# Cisco-Console-CP2102-Piggyback.net
KiCad netlist of a schematic drawn in EAGLE
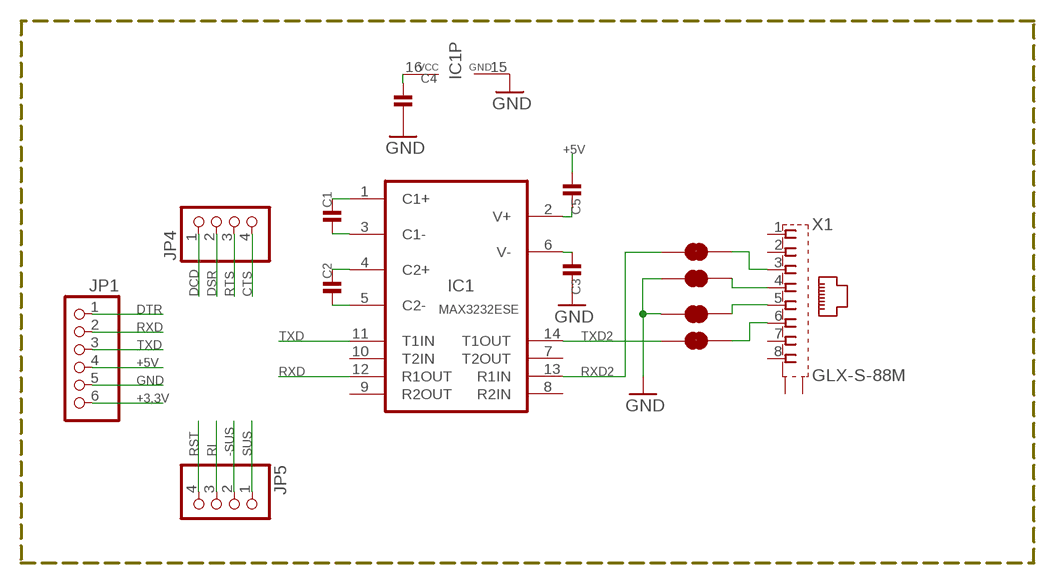
[diagram p0: schematic, sheet 1]

(export (version "E")
  (design (tool "Eeschema 10.0.6"))
  (components
    (comp (ref "C1")
      (value "MICROBUILDER_CAP_CERAMIC0402")
      (footprint "eagle-import:MICROBUILDER_0402")
      (libsource (lib "eagle-import") (part "MICROBUILDER_CAP_CERAMIC0402"))
    )
    (comp (ref "C2")
      (value "MICROBUILDER_CAP_CERAMIC0402")
      (footprint "eagle-import:MICROBUILDER_0402")
      (libsource (lib "eagle-import") (part "MICROBUILDER_CAP_CERAMIC0402"))
    )
    (comp (ref "C3")
      (value "MICROBUILDER_CAP_CERAMIC0402")
      (footprint "eagle-import:MICROBUILDER_0402")
      (libsource (lib "eagle-import") (part "MICROBUILDER_CAP_CERAMIC0402"))
    )
    (comp (ref "C4")
      (value "MICROBUILDER_CAP_CERAMIC0402")
      (footprint "eagle-import:MICROBUILDER_0402")
      (libsource (lib "eagle-import") (part "MICROBUILDER_CAP_CERAMIC0402"))
    )
    (comp (ref "C5")
      (value "MICROBUILDER_CAP_CERAMIC0402")
      (footprint "eagle-import:MICROBUILDER_0402")
      (libsource (lib "eagle-import") (part "MICROBUILDER_CAP_CERAMIC0402"))
    )
    (comp (ref "IC1")
      (value "MAX3232ESE")
      (footprint "eagle-import:SO16")
      (fields (field (name "MF") "MAXIM"))
      (libsource (lib "eagle-import") (part "MAX3232SEE"))
    )
    (comp (ref "JP1")
      (value "PINHD-1X6")
      (footprint "eagle-import:1X06")
      (libsource (lib "eagle-import") (part "PINHD-1X6"))
    )
    (comp (ref "JP4")
      (value "PINHD-1X4")
      (footprint "eagle-import:1X04")
      (libsource (lib "eagle-import") (part "PINHD-1X4"))
    )
    (comp (ref "JP5")
      (value "PINHD-1X4")
      (footprint "eagle-import:1X04")
      (libsource (lib "eagle-import") (part "PINHD-1X4"))
    )
    (comp (ref "JP6")
      (value "JUMPER-SMT_2_NC_TRACE_NO-SILK")
      (footprint "eagle-import:SMT-JUMPER_2_NC_TRACE_NO-SILK")
      (libsource (lib "eagle-import") (part "JUMPER-SMT_2_NC_TRACE_NO-SILK"))
    )
    (comp (ref "JP7")
      (value "JUMPER-SMT_2_NC_TRACE_NO-SILK")
      (footprint "eagle-import:SMT-JUMPER_2_NC_TRACE_NO-SILK")
      (libsource (lib "eagle-import") (part "JUMPER-SMT_2_NC_TRACE_NO-SILK"))
    )
    (comp (ref "JP8")
      (value "JUMPER-SMT_2_NC_TRACE_NO-SILK")
      (footprint "eagle-import:SMT-JUMPER_2_NC_TRACE_NO-SILK")
      (libsource (lib "eagle-import") (part "JUMPER-SMT_2_NC_TRACE_NO-SILK"))
    )
    (comp (ref "JP9")
      (value "JUMPER-SMT_2_NC_TRACE_NO-SILK")
      (footprint "eagle-import:SMT-JUMPER_2_NC_TRACE_NO-SILK")
      (libsource (lib "eagle-import") (part "JUMPER-SMT_2_NC_TRACE_NO-SILK"))
    )
    (comp (ref "X1")
      (value "GLX-S-88M")
      (footprint "eagle-import:GLX-S-88M")
      (libsource (lib "eagle-import") (part "GLX-S-88M"))
    )
  )
  (nets
    (net (code "1") (name "/+3,3V") (class "Default")
      (node (ref "JP1") (pin "6") (pinfunction "6_6") (pintype "passive"))
    )
    (net (code "2") (name "/+5V") (class "Default")
      (node (ref "C5") (pin "1") (pinfunction "P$1_1") (pintype "passive"))
      (node (ref "JP1") (pin "4") (pinfunction "4_4") (pintype "passive"))
    )
    (net (code "3") (name "/-SUS") (class "Default")
      (node (ref "JP5") (pin "2") (pinfunction "2_2") (pintype "passive"))
    )
    (net (code "4") (name "/CTS") (class "Default")
      (node (ref "JP4") (pin "4") (pinfunction "4_4") (pintype "passive"))
    )
    (net (code "5") (name "/DCD") (class "Default")
      (node (ref "JP4") (pin "1") (pinfunction "1_1") (pintype "passive"))
    )
    (net (code "6") (name "/DSR") (class "Default")
      (node (ref "JP4") (pin "2") (pinfunction "2_2") (pintype "passive"))
    )
    (net (code "7") (name "/DTR") (class "Default")
      (node (ref "JP1") (pin "1") (pinfunction "1_1") (pintype "passive"))
    )
    (net (code "8") (name "/RI") (class "Default")
      (node (ref "JP5") (pin "3") (pinfunction "3_3") (pintype "passive"))
    )
    (net (code "9") (name "/RST") (class "Default")
      (node (ref "JP5") (pin "4") (pinfunction "4_4") (pintype "passive"))
    )
    (net (code "10") (name "/RTS") (class "Default")
      (node (ref "JP4") (pin "3") (pinfunction "3_3") (pintype "passive"))
    )
    (net (code "11") (name "/RXD") (class "Default")
      (node (ref "IC1") (pin "12") (pinfunction "R1OUT_12") (pintype "output"))
      (node (ref "JP1") (pin "2") (pinfunction "2_2") (pintype "passive"))
    )
    (net (code "12") (name "/RXD2") (class "Default")
      (node (ref "IC1") (pin "13") (pinfunction "R1IN_13") (pintype "input"))
      (node (ref "JP6") (pin "1") (pinfunction "1_1") (pintype "passive"))
    )
    (net (code "13") (name "/SUS") (class "Default")
      (node (ref "JP5") (pin "1") (pinfunction "1_1") (pintype "passive"))
    )
    (net (code "14") (name "/TXD") (class "Default")
      (node (ref "IC1") (pin "11") (pinfunction "T1IN_11") (pintype "input"))
      (node (ref "JP1") (pin "3") (pinfunction "3_3") (pintype "passive"))
    )
    (net (code "15") (name "/TXD2") (class "Default")
      (node (ref "IC1") (pin "14") (pinfunction "T1OUT_14") (pintype "output"))
      (node (ref "JP9") (pin "1") (pinfunction "1_1") (pintype "passive"))
    )
    (net (code "16") (name "GND") (class "Default")
      (node (ref "C3") (pin "2") (pinfunction "P$2_2") (pintype "passive"))
      (node (ref "C4") (pin "2") (pinfunction "P$2_2") (pintype "passive"))
      (node (ref "IC1") (pin "15") (pinfunction "GND_15") (pintype "power_in"))
      (node (ref "JP1") (pin "5") (pinfunction "5_5") (pintype "passive"))
      (node (ref "JP7") (pin "1") (pinfunction "1_1") (pintype "passive"))
      (node (ref "JP8") (pin "1") (pinfunction "1_1") (pintype "passive"))
    )
    (net (code "17") (name "Net-(C1-P$1)") (class "Default")
      (node (ref "C1") (pin "1") (pinfunction "P$1_1") (pintype "passive"))
      (node (ref "IC1") (pin "1") (pinfunction "C1+_1") (pintype "bidirectional"))
    )
    (net (code "18") (name "Net-(C1-P$2)") (class "Default")
      (node (ref "C1") (pin "2") (pinfunction "P$2_2") (pintype "passive"))
      (node (ref "IC1") (pin "3") (pinfunction "C1-_3") (pintype "bidirectional"))
    )
    (net (code "19") (name "Net-(C2-P$1)") (class "Default")
      (node (ref "C2") (pin "1") (pinfunction "P$1_1") (pintype "passive"))
      (node (ref "IC1") (pin "4") (pinfunction "C2+_4") (pintype "bidirectional"))
    )
    (net (code "20") (name "Net-(C2-P$2)") (class "Default")
      (node (ref "C2") (pin "2") (pinfunction "P$2_2") (pintype "passive"))
      (node (ref "IC1") (pin "5") (pinfunction "C2-_5") (pintype "bidirectional"))
    )
    (net (code "21") (name "Net-(C3-P$1)") (class "Default")
      (node (ref "C3") (pin "1") (pinfunction "P$1_1") (pintype "passive"))
      (node (ref "IC1") (pin "6") (pinfunction "V-_6") (pintype "bidirectional"))
    )
    (net (code "22") (name "Net-(C4-P$1)") (class "Default")
      (node (ref "C4") (pin "1") (pinfunction "P$1_1") (pintype "passive"))
      (node (ref "IC1") (pin "16") (pinfunction "VCC_16") (pintype "power_in"))
    )
    (net (code "23") (name "Net-(C5-P$2)") (class "Default")
      (node (ref "C5") (pin "2") (pinfunction "P$2_2") (pintype "passive"))
      (node (ref "IC1") (pin "2") (pinfunction "V+_2") (pintype "bidirectional"))
    )
    (net (code "24") (name "Net-(JP6-Pad2)") (class "Default")
      (node (ref "JP6") (pin "2") (pinfunction "2_2") (pintype "passive"))
      (node (ref "X1") (pin "3") (pinfunction "3_3") (pintype "passive"))
    )
    (net (code "25") (name "Net-(JP7-Pad2)") (class "Default")
      (node (ref "JP7") (pin "2") (pinfunction "2_2") (pintype "passive"))
      (node (ref "X1") (pin "4") (pinfunction "4_4") (pintype "passive"))
    )
    (net (code "26") (name "Net-(JP8-Pad2)") (class "Default")
      (node (ref "JP8") (pin "2") (pinfunction "2_2") (pintype "passive"))
      (node (ref "X1") (pin "5") (pinfunction "5_5") (pintype "passive"))
    )
    (net (code "27") (name "Net-(JP9-Pad2)") (class "Default")
      (node (ref "JP9") (pin "2") (pinfunction "2_2") (pintype "passive"))
      (node (ref "X1") (pin "6") (pinfunction "6_6") (pintype "passive"))
    )
    (net (code "28") (name "unconnected-(IC1A-R2IN-Pad8)") (class "Default")
      (node (ref "IC1") (pin "8") (pinfunction "R2IN_8") (pintype "input"))
    )
    (net (code "29") (name "unconnected-(IC1A-R2OUT-Pad9)") (class "Default")
      (node (ref "IC1") (pin "9") (pinfunction "R2OUT_9") (pintype "output"))
    )
    (net (code "30") (name "unconnected-(IC1A-T2IN-Pad10)") (class "Default")
      (node (ref "IC1") (pin "10") (pinfunction "T2IN_10") (pintype "input"))
    )
    (net (code "31") (name "unconnected-(IC1A-T2OUT-Pad7)") (class "Default")
      (node (ref "IC1") (pin "7") (pinfunction "T2OUT_7") (pintype "output"))
    )
    (net (code "32") (name "unconnected-(X1-Pad1)") (class "Default")
      (node (ref "X1") (pin "1") (pinfunction "1_1") (pintype "passive"))
    )
    (net (code "33") (name "unconnected-(X1-Pad2)") (class "Default")
      (node (ref "X1") (pin "2") (pinfunction "2_2") (pintype "passive"))
    )
    (net (code "34") (name "unconnected-(X1-Pad7)") (class "Default")
      (node (ref "X1") (pin "7") (pinfunction "7_7") (pintype "passive"))
    )
    (net (code "35") (name "unconnected-(X1-Pad8)") (class "Default")
      (node (ref "X1") (pin "8") (pinfunction "8_8") (pintype "passive"))
    )
    (net (code "36") (name "unconnected-(X1-PadS1)") (class "Default")
      (node (ref "X1") (pin "S1") (pinfunction "S1_S1") (pintype "passive"))
    )
    (net (code "37") (name "unconnected-(X1-PadS2)") (class "Default")
      (node (ref "X1") (pin "S2") (pinfunction "S2_S2") (pintype "passive"))
    )
  )
)
